# uC.net
KiCad netlist of a schematic drawn in Altium Designer
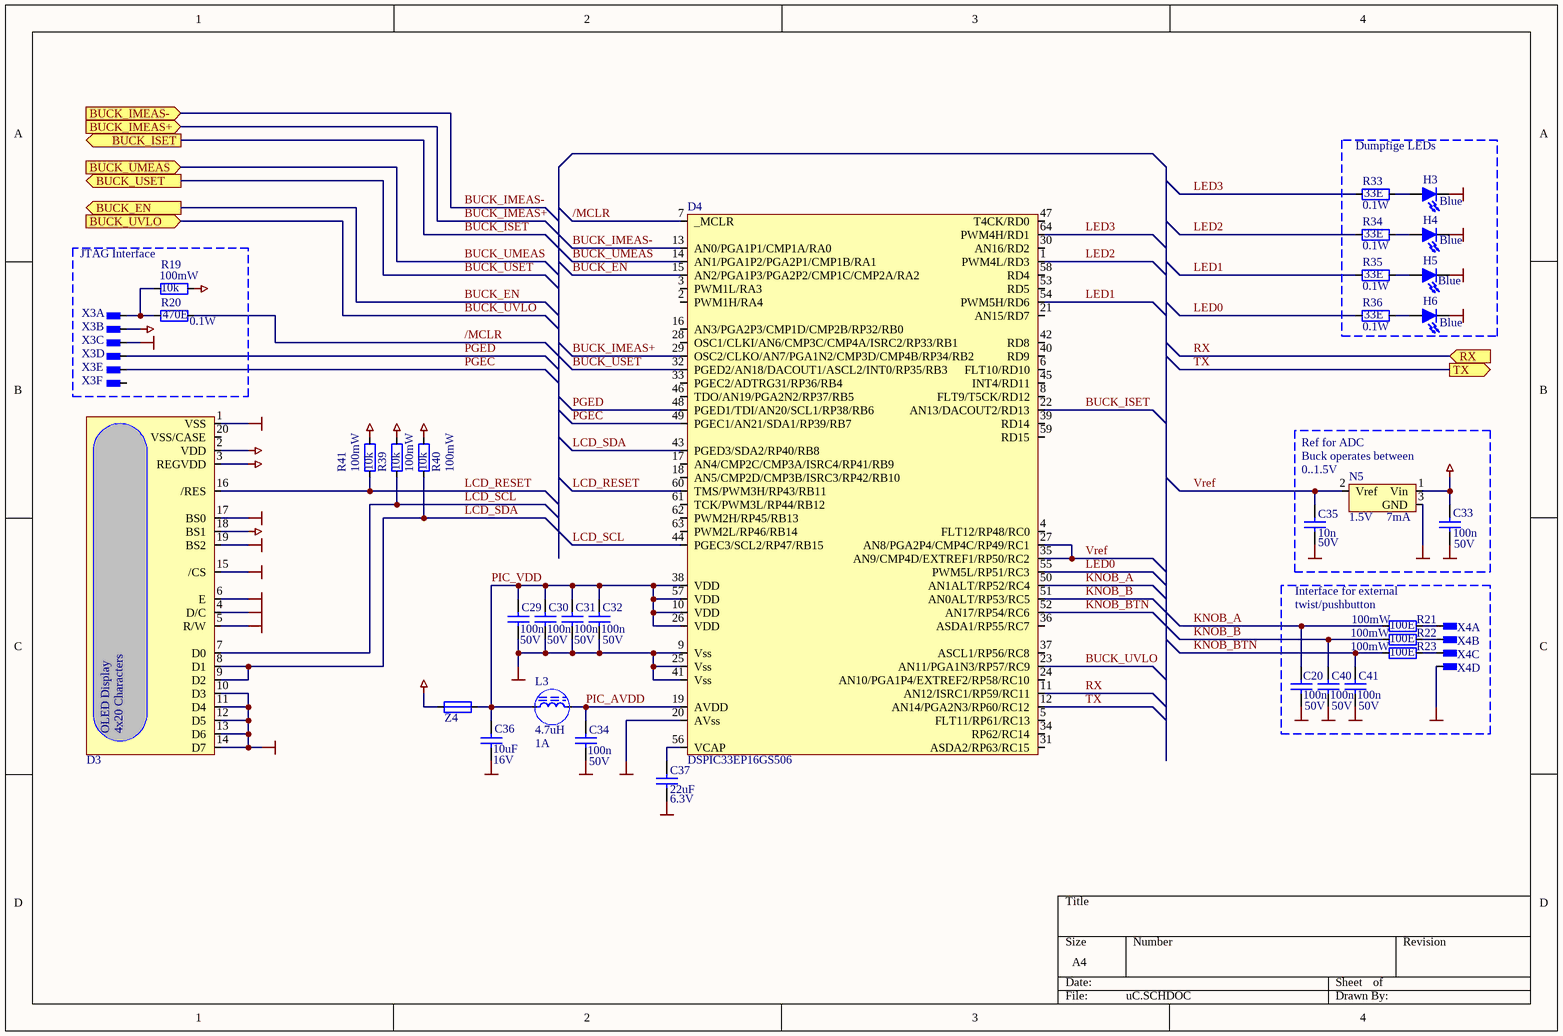
[diagram p0: uC.SCHDOC]

(export (version "E")
  (design (tool "Eeschema 10.0.6"))
  (components
    (comp (ref "C20")
      (value "C_SMD_CER_100N_50V_10%_X7R_0603")
      (footprint "SMD_0603")
      (description "SMD Capacitor")
      (fields (field (name "ALTIUM_VALUE") "100n") (field (name "VALUE2") "50V"))
      (libsource (lib "C-Capacitor") (part "C_SMD_CER_100N_50V_10%_X7R_0603"))
    )
    (comp (ref "C29")
      (value "C_SMD_CER_100N_50V_10%_X7R_0603")
      (footprint "SMD_0603")
      (description "SMD Capacitor")
      (fields (field (name "ALTIUM_VALUE") "100n") (field (name "VALUE2") "50V"))
      (libsource (lib "C-Capacitor") (part "C_SMD_CER_100N_50V_10%_X7R_0603"))
    )
    (comp (ref "C30")
      (value "C_SMD_CER_100N_50V_10%_X7R_0603")
      (footprint "SMD_0603")
      (description "SMD Capacitor")
      (fields (field (name "ALTIUM_VALUE") "100n") (field (name "VALUE2") "50V"))
      (libsource (lib "C-Capacitor") (part "C_SMD_CER_100N_50V_10%_X7R_0603"))
    )
    (comp (ref "C31")
      (value "C_SMD_CER_100N_50V_10%_X7R_0603")
      (footprint "SMD_0603")
      (description "SMD Capacitor")
      (fields (field (name "ALTIUM_VALUE") "100n") (field (name "VALUE2") "50V"))
      (libsource (lib "C-Capacitor") (part "C_SMD_CER_100N_50V_10%_X7R_0603"))
    )
    (comp (ref "C32")
      (value "C_SMD_CER_100N_50V_10%_X7R_0603")
      (footprint "SMD_0603")
      (description "SMD Capacitor")
      (fields (field (name "ALTIUM_VALUE") "100n") (field (name "VALUE2") "50V"))
      (libsource (lib "C-Capacitor") (part "C_SMD_CER_100N_50V_10%_X7R_0603"))
    )
    (comp (ref "C33")
      (value "C_SMD_CER_100N_50V_10%_X7R_0603")
      (footprint "SMD_0603")
      (description "SMD Capacitor")
      (fields (field (name "ALTIUM_VALUE") "100n") (field (name "VALUE2") "50V"))
      (libsource (lib "C-Capacitor") (part "C_SMD_CER_100N_50V_10%_X7R_0603"))
    )
    (comp (ref "C34")
      (value "C_SMD_CER_100N_50V_10%_X7R_0603")
      (footprint "SMD_0603")
      (description "SMD Capacitor")
      (fields (field (name "ALTIUM_VALUE") "100n") (field (name "VALUE2") "50V"))
      (libsource (lib "C-Capacitor") (part "C_SMD_CER_100N_50V_10%_X7R_0603"))
    )
    (comp (ref "C35")
      (value "C_SMD_CER_10N_50V_10%_X7R_0603")
      (footprint "SMD_0603")
      (description "SMD Capacitor")
      (fields (field (name "ALTIUM_VALUE") "10n") (field (name "VALUE2") "50V"))
      (libsource (lib "C-Capacitor") (part "C_SMD_CER_10N_50V_10%_X7R_0603"))
    )
    (comp (ref "C36")
      (value "C_SMD_CER_10U_16V_10%_X5R_0805")
      (footprint "SMD_0805")
      (description "SMD Capacitor")
      (fields (field (name "ALTIUM_VALUE") "10uF") (field (name "VALUE2") "16V"))
      (libsource (lib "C-Capacitor") (part "C_SMD_CER_10U_16V_10%_X5R_0805"))
    )
    (comp (ref "C37")
      (value "C_SMD_CER_22U_6V3_20%_X5R_1206")
      (footprint "SMD_1206")
      (description "SMD Capacitor")
      (fields (field (name "ALTIUM_VALUE") "22uF") (field (name "VALUE2") "6.3V"))
      (libsource (lib "C-Capacitor") (part "C_SMD_CER_22U_6V3_20%_X5R_1206"))
    )
    (comp (ref "C40")
      (value "C_SMD_CER_100N_50V_10%_X7R_0603")
      (footprint "SMD_0603")
      (description "SMD Capacitor")
      (fields (field (name "ALTIUM_VALUE") "100n") (field (name "VALUE2") "50V"))
      (libsource (lib "C-Capacitor") (part "C_SMD_CER_100N_50V_10%_X7R_0603"))
    )
    (comp (ref "C41")
      (value "C_SMD_CER_100N_50V_10%_X7R_0603")
      (footprint "SMD_0603")
      (description "SMD Capacitor")
      (fields (field (name "ALTIUM_VALUE") "100n") (field (name "VALUE2") "50V"))
      (libsource (lib "C-Capacitor") (part "C_SMD_CER_100N_50V_10%_X7R_0603"))
    )
    (comp (ref "D3")
      (value "D_LCD_80CHAR_20X4_NHD-0420CW-AR3")
      (footprint "THT_CON_P2.54_D0.9_2X10")
      (libsource (lib "D-Digital") (part "D_LCD_80CHAR_20X4_NHD-0420CW-AR3"))
    )
    (comp (ref "D4")
      (value "D_DSPIC33EP16GS506_TQFP-64")
      (footprint "SMD_TQFP-64")
      (fields (field (name "TYPE") "DSPIC33EP16GS506"))
      (libsource (lib "AM") (part "D_DSPIC33EP16GS506_TQFP-64"))
    )
    (comp (ref "H3")
      (value "H_SMD_LED_BLUE_0603")
      (footprint "SMD_0603P")
      (description "Blue LED, 5mA")
      (fields (field (name "TYPE") "Blue"))
      (libsource (lib "H-Signaling device") (part "H_SMD_LED_BLUE_0603"))
    )
    (comp (ref "H4")
      (value "H_SMD_LED_BLUE_0603")
      (footprint "SMD_0603P")
      (description "Blue LED, 5mA")
      (fields (field (name "TYPE") "Blue"))
      (libsource (lib "H-Signaling device") (part "H_SMD_LED_BLUE_0603"))
    )
    (comp (ref "H5")
      (value "H_SMD_LED_BLUE_0603")
      (footprint "SMD_0603P")
      (description "Blue LED, 5mA")
      (fields (field (name "TYPE") "Blue"))
      (libsource (lib "H-Signaling device") (part "H_SMD_LED_BLUE_0603"))
    )
    (comp (ref "H6")
      (value "H_SMD_LED_BLUE_0603")
      (footprint "SMD_0603P")
      (description "Blue LED, 5mA")
      (fields (field (name "TYPE") "Blue"))
      (libsource (lib "H-Signaling device") (part "H_SMD_LED_BLUE_0603"))
    )
    (comp (ref "L3")
      (value "L_SMD_4U7_1A_20%_0806")
      (footprint "SMD_0806")
      (description "SMD Inductor")
      (fields (field (name "ALTIUM_VALUE") "4.7uH") (field (name "VALUE2") "1A"))
      (libsource (lib "AM") (part "L_SMD_4U7_1A_20%_0806"))
    )
    (comp (ref "N5")
      (value "N_UREF_1V5_0A007_52UVRMS_ISL21080CIH315Z_SOT-23-3")
      (footprint "SMD_SOT_23_3")
      (fields (field (name "ALTIUM_VALUE") "1.5V") (field (name "VALUE2") "7mA"))
      (libsource (lib "AM") (part "N_UREF_1V5_0A007_52UVRMS_ISL21080CIH315Z_SOT-23-3"))
    )
    (comp (ref "R19")
      (value "R_SMD_THINFILM_10K_0W1_1%_50PPM_0603")
      (footprint "SMD_0603")
      (description "SMD Resistor")
      (fields (field (name "ALTIUM_VALUE") "10k") (field (name "VALUE2") "100mW"))
      (libsource (lib "R-Resistor") (part "R_SMD_THINFILM_10K_0W1_1%_50PPM_0603"))
    )
    (comp (ref "R20")
      (value "R_SMD_THINFILM_470E_0W1_1%_50PPM_0603")
      (footprint "SMD_0603")
      (description "SMD Resistor")
      (fields (field (name "ALTIUM_VALUE") "470E") (field (name "VALUE2") "0.1W"))
      (libsource (lib "AM") (part "R_SMD_THINFILM_470E_0W1_1%_50PPM_0603"))
    )
    (comp (ref "R21")
      (value "R_SMD_THINFILM_100E_0W1_1%_50PPM_0603")
      (footprint "SMD_0603")
      (description "SMD Resistor")
      (fields (field (name "ALTIUM_VALUE") "100E") (field (name "VALUE2") "100mW"))
      (libsource (lib "R-Resistor") (part "R_SMD_THINFILM_100E_0W1_1%_50PPM_0603"))
    )
    (comp (ref "R22")
      (value "R_SMD_THINFILM_100E_0W1_1%_50PPM_0603")
      (footprint "SMD_0603")
      (description "SMD Resistor")
      (fields (field (name "ALTIUM_VALUE") "100E") (field (name "VALUE2") "100mW"))
      (libsource (lib "R-Resistor") (part "R_SMD_THINFILM_100E_0W1_1%_50PPM_0603"))
    )
    (comp (ref "R23")
      (value "R_SMD_THINFILM_100E_0W1_1%_50PPM_0603")
      (footprint "SMD_0603")
      (description "SMD Resistor")
      (fields (field (name "ALTIUM_VALUE") "100E") (field (name "VALUE2") "100mW"))
      (libsource (lib "R-Resistor") (part "R_SMD_THINFILM_100E_0W1_1%_50PPM_0603"))
    )
    (comp (ref "R33")
      (value "R_SMD_THINFILM_33E_0W1_1%_50PPM_0603")
      (footprint "SMD_0603")
      (description "SMD Resistor")
      (fields (field (name "ALTIUM_VALUE") "33E") (field (name "VALUE2") "0.1W"))
      (libsource (lib "R-Resistor") (part "R_SMD_THINFILM_33E_0W1_1%_50PPM_0603"))
    )
    (comp (ref "R34")
      (value "R_SMD_THINFILM_33E_0W1_1%_50PPM_0603")
      (footprint "SMD_0603")
      (description "SMD Resistor")
      (fields (field (name "ALTIUM_VALUE") "33E") (field (name "VALUE2") "0.1W"))
      (libsource (lib "R-Resistor") (part "R_SMD_THINFILM_33E_0W1_1%_50PPM_0603"))
    )
    (comp (ref "R35")
      (value "R_SMD_THINFILM_33E_0W1_1%_50PPM_0603")
      (footprint "SMD_0603")
      (description "SMD Resistor")
      (fields (field (name "ALTIUM_VALUE") "33E") (field (name "VALUE2") "0.1W"))
      (libsource (lib "R-Resistor") (part "R_SMD_THINFILM_33E_0W1_1%_50PPM_0603"))
    )
    (comp (ref "R36")
      (value "R_SMD_THINFILM_33E_0W1_1%_50PPM_0603")
      (footprint "SMD_0603")
      (description "SMD Resistor")
      (fields (field (name "ALTIUM_VALUE") "33E") (field (name "VALUE2") "0.1W"))
      (libsource (lib "R-Resistor") (part "R_SMD_THINFILM_33E_0W1_1%_50PPM_0603"))
    )
    (comp (ref "R39")
      (value "R_SMD_THINFILM_10K_0W1_1%_50PPM_0603")
      (footprint "SMD_0603")
      (description "SMD Resistor")
      (fields (field (name "ALTIUM_VALUE") "10k") (field (name "VALUE2") "100mW"))
      (libsource (lib "AM") (part "R_SMD_THINFILM_10K_0W1_1%_50PPM_0603"))
    )
    (comp (ref "R40")
      (value "R_SMD_THINFILM_10K_0W1_1%_50PPM_0603")
      (footprint "SMD_0603")
      (description "SMD Resistor")
      (fields (field (name "ALTIUM_VALUE") "10k") (field (name "VALUE2") "100mW"))
      (libsource (lib "AM") (part "R_SMD_THINFILM_10K_0W1_1%_50PPM_0603"))
    )
    (comp (ref "R41")
      (value "R_SMD_THINFILM_10K_0W1_1%_50PPM_0603")
      (footprint "SMD_0603")
      (description "SMD Resistor")
      (fields (field (name "ALTIUM_VALUE") "10k") (field (name "VALUE2") "100mW"))
      (libsource (lib "AM") (part "R_SMD_THINFILM_10K_0W1_1%_50PPM_0603"))
    )
    (comp (ref "X3")
      (value "X_CONNECTOR_P2.54_D0.9_1X6")
      (footprint "THT_CON_P2.54_D0.9_1X6")
      (description "Pitch 2.54, Diameter 0.9mm, 1 row, 6 columns")
      (libsource (lib "AM") (part "X_CONNECTOR_P2.54_D0.9_1X6"))
    )
    (comp (ref "X4")
      (value "X_CONNECTOR_P2.54_D0.9_1X4")
      (footprint "THT_CON_P2.54_D0.9_1X4")
      (description "Pitch 2.54, Diameter 0.9mm, 1 row, 4 columns")
      (libsource (lib "AM") (part "X_CONNECTOR_P2.54_D0.9_1X4"))
    )
    (comp (ref "Z4")
      (value "Z_SMD_FERRITE_1A5_470E@100MHZ_0603")
      (footprint "SMD_0603")
      (description "FERRITE CHIP 470 OHM 1500MA 0603")
      (libsource (lib "AM") (part "Z_SMD_FERRITE_1A5_470E@100MHZ_0603"))
    )
  )
  (nets
    (net (code "1") (name "+3.3V") (class "Default")
      (node (ref "C33") (pin "2") (pinfunction "2_2") (pintype "passive"))
      (node (ref "N5") (pin "1") (pinfunction "Vin_1") (pintype "passive"))
      (node (ref "R19") (pin "2") (pinfunction "2_2") (pintype "passive"))
      (node (ref "X3") (pin "2") (pinfunction "2_2") (pintype "passive"))
      (node (ref "Z4") (pin "2") (pinfunction "2_2") (pintype "passive"))
    )
    (net (code "2") (name "+5V") (class "Default")
      (node (ref "D3") (pin "18") (pinfunction "BS1_18") (pintype "passive"))
      (node (ref "D3") (pin "2") (pinfunction "VDD_2") (pintype "passive"))
      (node (ref "D3") (pin "3") (pinfunction "REGVDD_3") (pintype "passive"))
      (node (ref "R39") (pin "2") (pinfunction "2_2") (pintype "passive"))
      (node (ref "R40") (pin "2") (pinfunction "2_2") (pintype "passive"))
      (node (ref "R41") (pin "2") (pinfunction "2_2") (pintype "passive"))
    )
    (net (code "3") (name "/BUCK_EN") (class "Default")
      (node (ref "D4") (pin "15") (pinfunction "AN2/PGA1P3/PGA2P2/CMP1C/CMP2A/RA2_15") (pintype "passive"))
    )
    (net (code "4") (name "/BUCK_IMEAS+") (class "Default")
      (node (ref "D4") (pin "29") (pinfunction "OSC2/CLKO/AN7/PGA1N2/CMP3D/CMP4B/RP34/RB2_29") (pintype "passive"))
    )
    (net (code "5") (name "/BUCK_IMEAS-") (class "Default")
      (node (ref "D4") (pin "13") (pinfunction "AN0/PGA1P1/CMP1A/RA0_13") (pintype "passive"))
    )
    (net (code "6") (name "/BUCK_ISET") (class "Default")
      (node (ref "D4") (pin "22") (pinfunction "AN13/DACOUT2/RD13_22") (pintype "passive"))
    )
    (net (code "7") (name "/BUCK_UMEAS") (class "Default")
      (node (ref "D4") (pin "14") (pinfunction "AN1/PGA1P2/PGA2P1/CMP1B/RA1_14") (pintype "passive"))
    )
    (net (code "8") (name "/BUCK_USET") (class "Default")
      (node (ref "D4") (pin "32") (pinfunction "PGED2/AN18/DACOUT1/ASCL2/INT0/RP35/RB3_32") (pintype "passive"))
    )
    (net (code "9") (name "/BUCK_UVLO") (class "Default")
      (node (ref "D4") (pin "23") (pinfunction "AN11/PGA1N3/RP57/RC9_23") (pintype "passive"))
    )
    (net (code "10") (name "/KNOB_A") (class "Default")
      (node (ref "C20") (pin "2") (pinfunction "2_2") (pintype "passive"))
      (node (ref "D4") (pin "50") (pinfunction "AN1ALT/RP52/RC4_50") (pintype "passive"))
      (node (ref "R21") (pin "1") (pinfunction "1_1") (pintype "passive"))
    )
    (net (code "11") (name "/KNOB_B") (class "Default")
      (node (ref "C40") (pin "2") (pinfunction "2_2") (pintype "passive"))
      (node (ref "D4") (pin "51") (pinfunction "AN0ALT/RP53/RC5_51") (pintype "passive"))
      (node (ref "R22") (pin "1") (pinfunction "1_1") (pintype "passive"))
    )
    (net (code "12") (name "/KNOB_BTN") (class "Default")
      (node (ref "C41") (pin "2") (pinfunction "2_2") (pintype "passive"))
      (node (ref "D4") (pin "52") (pinfunction "AN17/RP54/RC6_52") (pintype "passive"))
      (node (ref "R23") (pin "1") (pinfunction "1_1") (pintype "passive"))
    )
    (net (code "13") (name "/LCD_RESET") (class "Default")
      (node (ref "D3") (pin "16") (pinfunction "/RES_16") (pintype "passive"))
      (node (ref "D4") (pin "60") (pinfunction "TMS/PWM3H/RP43/RB11_60") (pintype "passive"))
      (node (ref "R41") (pin "1") (pinfunction "1_1") (pintype "passive"))
    )
    (net (code "14") (name "/LCD_SCL") (class "Default")
      (node (ref "D3") (pin "7") (pinfunction "D0_7") (pintype "passive"))
      (node (ref "D4") (pin "44") (pinfunction "PGEC3/SCL2/RP47/RB15_44") (pintype "passive"))
      (node (ref "R39") (pin "1") (pinfunction "1_1") (pintype "passive"))
    )
    (net (code "15") (name "/LCD_SDA") (class "Default")
      (node (ref "D3") (pin "8") (pinfunction "D1_8") (pintype "passive"))
      (node (ref "D3") (pin "9") (pinfunction "D2_9") (pintype "passive"))
      (node (ref "D4") (pin "43") (pinfunction "PGED3/SDA2/RP40/RB8_43") (pintype "passive"))
      (node (ref "R40") (pin "1") (pinfunction "1_1") (pintype "passive"))
    )
    (net (code "16") (name "/LED0") (class "Default")
      (node (ref "D4") (pin "55") (pinfunction "PWM5L/RP51/RC3_55") (pintype "passive"))
      (node (ref "R36") (pin "1") (pinfunction "1_1") (pintype "passive"))
    )
    (net (code "17") (name "/LED1") (class "Default")
      (node (ref "D4") (pin "54") (pinfunction "PWM5H/RD6_54") (pintype "passive"))
      (node (ref "R35") (pin "1") (pinfunction "1_1") (pintype "passive"))
    )
    (net (code "18") (name "/LED2") (class "Default")
      (node (ref "D4") (pin "1") (pinfunction "PWM4L/RD3_1") (pintype "passive"))
      (node (ref "R34") (pin "1") (pinfunction "1_1") (pintype "passive"))
    )
    (net (code "19") (name "/LED3") (class "Default")
      (node (ref "D4") (pin "64") (pinfunction "PWM4H/RD1_64") (pintype "passive"))
      (node (ref "R33") (pin "1") (pinfunction "1_1") (pintype "passive"))
    )
    (net (code "20") (name "/PGEC") (class "Default")
      (node (ref "D4") (pin "49") (pinfunction "PGEC1/AN21/SDA1/RP39/RB7_49") (pintype "passive"))
      (node (ref "X3") (pin "5") (pinfunction "5_5") (pintype "passive"))
    )
    (net (code "21") (name "/PGED") (class "Default")
      (node (ref "D4") (pin "48") (pinfunction "PGED1/TDI/AN20/SCL1/RP38/RB6_48") (pintype "passive"))
      (node (ref "X3") (pin "4") (pinfunction "4_4") (pintype "passive"))
    )
    (net (code "22") (name "/PIC_AVDD") (class "Default")
      (node (ref "C34") (pin "2") (pinfunction "2_2") (pintype "passive"))
      (node (ref "D4") (pin "19") (pinfunction "AVDD_19") (pintype "passive"))
      (node (ref "L3") (pin "2") (pinfunction "2_2") (pintype "passive"))
    )
    (net (code "23") (name "/PIC_VDD") (class "Default")
      (node (ref "C29") (pin "2") (pinfunction "2_2") (pintype "passive"))
      (node (ref "C30") (pin "2") (pinfunction "2_2") (pintype "passive"))
      (node (ref "C31") (pin "2") (pinfunction "2_2") (pintype "passive"))
      (node (ref "C32") (pin "2") (pinfunction "2_2") (pintype "passive"))
      (node (ref "C36") (pin "2") (pinfunction "2_2") (pintype "passive"))
      (node (ref "D4") (pin "10") (pinfunction "VDD_10") (pintype "passive"))
      (node (ref "D4") (pin "26") (pinfunction "VDD_26") (pintype "passive"))
      (node (ref "D4") (pin "38") (pinfunction "VDD_38") (pintype "passive"))
      (node (ref "D4") (pin "57") (pinfunction "VDD_57") (pintype "passive"))
      (node (ref "L3") (pin "1") (pinfunction "1_1") (pintype "passive"))
      (node (ref "Z4") (pin "1") (pinfunction "1_1") (pintype "passive"))
    )
    (net (code "24") (name "/RX") (class "Default")
      (node (ref "D4") (pin "11") (pinfunction "AN12/ISRC1/RP59/RC11_11") (pintype "passive"))
    )
    (net (code "25") (name "/TX") (class "Default")
      (node (ref "D4") (pin "12") (pinfunction "AN14/PGA2N3/RP60/RC12_12") (pintype "passive"))
    )
    (net (code "26") (name "/Vref") (class "Default")
      (node (ref "C35") (pin "2") (pinfunction "2_2") (pintype "passive"))
      (node (ref "D4") (pin "27") (pinfunction "AN8/PGA2P4/CMP4C/RP49/RC1_27") (pintype "passive"))
      (node (ref "D4") (pin "35") (pinfunction "AN9/CMP4D/EXTREF1/RP50/RC2_35") (pintype "passive"))
      (node (ref "N5") (pin "2") (pinfunction "Vref_2") (pintype "passive"))
    )
    (net (code "27") (name "/{slash}MCLR") (class "Default")
      (node (ref "D4") (pin "7") (pinfunction "_MCLR_7") (pintype "passive"))
      (node (ref "R20") (pin "2") (pinfunction "2_2") (pintype "passive"))
    )
    (net (code "28") (name "GND") (class "Default")
      (node (ref "C20") (pin "1") (pinfunction "1_1") (pintype "passive"))
      (node (ref "C29") (pin "1") (pinfunction "1_1") (pintype "passive"))
      (node (ref "C30") (pin "1") (pinfunction "1_1") (pintype "passive"))
      (node (ref "C31") (pin "1") (pinfunction "1_1") (pintype "passive"))
      (node (ref "C32") (pin "1") (pinfunction "1_1") (pintype "passive"))
      (node (ref "C33") (pin "1") (pinfunction "1_1") (pintype "passive"))
      (node (ref "C34") (pin "1") (pinfunction "1_1") (pintype "passive"))
      (node (ref "C35") (pin "1") (pinfunction "1_1") (pintype "passive"))
      (node (ref "C36") (pin "1") (pinfunction "1_1") (pintype "passive"))
      (node (ref "C37") (pin "1") (pinfunction "1_1") (pintype "passive"))
      (node (ref "C40") (pin "1") (pinfunction "1_1") (pintype "passive"))
      (node (ref "C41") (pin "1") (pinfunction "1_1") (pintype "passive"))
      (node (ref "D3") (pin "1") (pinfunction "VSS_1") (pintype "passive"))
      (node (ref "D3") (pin "10") (pinfunction "D3_10") (pintype "passive"))
      (node (ref "D3") (pin "11") (pinfunction "D4_11") (pintype "passive"))
      (node (ref "D3") (pin "12") (pinfunction "D5_12") (pintype "passive"))
      (node (ref "D3") (pin "13") (pinfunction "D6_13") (pintype "passive"))
      (node (ref "D3") (pin "14") (pinfunction "D7_14") (pintype "passive"))
      (node (ref "D3") (pin "15") (pinfunction "/CS_15") (pintype "passive"))
      (node (ref "D3") (pin "17") (pinfunction "BS0_17") (pintype "passive"))
      (node (ref "D3") (pin "19") (pinfunction "BS2_19") (pintype "passive"))
      (node (ref "D3") (pin "4") (pinfunction "D/C_4") (pintype "passive"))
      (node (ref "D3") (pin "5") (pinfunction "R/W_5") (pintype "passive"))
      (node (ref "D3") (pin "6") (pinfunction "E_6") (pintype "passive"))
      (node (ref "D4") (pin "20") (pinfunction "AVss_20") (pintype "passive"))
      (node (ref "D4") (pin "25") (pinfunction "Vss_25") (pintype "passive"))
      (node (ref "D4") (pin "41") (pinfunction "Vss_41") (pintype "passive"))
      (node (ref "D4") (pin "9") (pinfunction "Vss_9") (pintype "passive"))
      (node (ref "H3") (pin "2") (pinfunction "2_2") (pintype "passive"))
      (node (ref "H4") (pin "2") (pinfunction "2_2") (pintype "passive"))
      (node (ref "H5") (pin "2") (pinfunction "2_2") (pintype "passive"))
      (node (ref "H6") (pin "2") (pinfunction "2_2") (pintype "passive"))
      (node (ref "N5") (pin "3") (pinfunction "GND_3") (pintype "passive"))
      (node (ref "X3") (pin "3") (pinfunction "3_3") (pintype "passive"))
      (node (ref "X4") (pin "4") (pinfunction "4_4") (pintype "passive"))
    )
    (net (code "29") (name "Net-(D4-VCAP)") (class "Default")
      (node (ref "C37") (pin "2") (pinfunction "2_2") (pintype "passive"))
      (node (ref "D4") (pin "56") (pinfunction "VCAP_56") (pintype "passive"))
    )
    (net (code "30") (name "Net-(H3-Pad1)") (class "Default")
      (node (ref "H3") (pin "1") (pinfunction "1_1") (pintype "passive"))
      (node (ref "R33") (pin "2") (pinfunction "2_2") (pintype "passive"))
    )
    (net (code "31") (name "Net-(H4-Pad1)") (class "Default")
      (node (ref "H4") (pin "1") (pinfunction "1_1") (pintype "passive"))
      (node (ref "R34") (pin "2") (pinfunction "2_2") (pintype "passive"))
    )
    (net (code "32") (name "Net-(H5-Pad1)") (class "Default")
      (node (ref "H5") (pin "1") (pinfunction "1_1") (pintype "passive"))
      (node (ref "R35") (pin "2") (pinfunction "2_2") (pintype "passive"))
    )
    (net (code "33") (name "Net-(H6-Pad1)") (class "Default")
      (node (ref "H6") (pin "1") (pinfunction "1_1") (pintype "passive"))
      (node (ref "R36") (pin "2") (pinfunction "2_2") (pintype "passive"))
    )
    (net (code "34") (name "Net-(R19-Pad1)") (class "Default")
      (node (ref "R19") (pin "1") (pinfunction "1_1") (pintype "passive"))
      (node (ref "R20") (pin "1") (pinfunction "1_1") (pintype "passive"))
      (node (ref "X3") (pin "1") (pinfunction "1_1") (pintype "passive"))
    )
    (net (code "35") (name "Net-(R21-Pad2)") (class "Default")
      (node (ref "R21") (pin "2") (pinfunction "2_2") (pintype "passive"))
      (node (ref "X4") (pin "1") (pinfunction "1_1") (pintype "passive"))
    )
    (net (code "36") (name "Net-(R22-Pad2)") (class "Default")
      (node (ref "R22") (pin "2") (pinfunction "2_2") (pintype "passive"))
      (node (ref "X4") (pin "2") (pinfunction "2_2") (pintype "passive"))
    )
    (net (code "37") (name "Net-(R23-Pad2)") (class "Default")
      (node (ref "R23") (pin "2") (pinfunction "2_2") (pintype "passive"))
      (node (ref "X4") (pin "3") (pinfunction "3_3") (pintype "passive"))
    )
    (net (code "38") (name "unconnected-(D3-VSS{slash}CASE-Pad20)") (class "Default")
      (node (ref "D3") (pin "20") (pinfunction "VSS/CASE_20") (pintype "passive"))
    )
    (net (code "39") (name "unconnected-(D4-AN3{slash}PGA2P3{slash}CMP1D{slash}CMP2B{slash}RP32{slash}RB0-Pad16)") (class "Default")
      (node (ref "D4") (pin "16") (pinfunction "AN3/PGA2P3/CMP1D/CMP2B/RP32/RB0_16") (pintype "passive"))
    )
    (net (code "40") (name "unconnected-(D4-AN4{slash}CMP2C{slash}CMP3A{slash}ISRC4{slash}RP41{slash}RB9-Pad17)") (class "Default")
      (node (ref "D4") (pin "17") (pinfunction "AN4/CMP2C/CMP3A/ISRC4/RP41/RB9_17") (pintype "passive"))
    )
    (net (code "41") (name "unconnected-(D4-AN5{slash}CMP2D{slash}CMP3B{slash}ISRC3{slash}RP42{slash}RB10-Pad18)") (class "Default")
      (node (ref "D4") (pin "18") (pinfunction "AN5/CMP2D/CMP3B/ISRC3/RP42/RB10_18") (pintype "passive"))
    )
    (net (code "42") (name "unconnected-(D4-AN10{slash}PGA1P4{slash}EXTREF2{slash}RP58{slash}RC10-Pad24)") (class "Default")
      (node (ref "D4") (pin "24") (pinfunction "AN10/PGA1P4/EXTREF2/RP58/RC10_24") (pintype "passive"))
    )
    (net (code "43") (name "unconnected-(D4-AN15{slash}RD7-Pad21)") (class "Default")
      (node (ref "D4") (pin "21") (pinfunction "AN15/RD7_21") (pintype "passive"))
    )
    (net (code "44") (name "unconnected-(D4-AN16{slash}RD2-Pad30)") (class "Default")
      (node (ref "D4") (pin "30") (pinfunction "AN16/RD2_30") (pintype "passive"))
    )
    (net (code "45") (name "unconnected-(D4-ASCL1{slash}RP56{slash}RC8-Pad37)") (class "Default")
      (node (ref "D4") (pin "37") (pinfunction "ASCL1/RP56/RC8_37") (pintype "passive"))
    )
    (net (code "46") (name "unconnected-(D4-ASDA1{slash}RP55{slash}RC7-Pad36)") (class "Default")
      (node (ref "D4") (pin "36") (pinfunction "ASDA1/RP55/RC7_36") (pintype "passive"))
    )
    (net (code "47") (name "unconnected-(D4-ASDA2{slash}RP63{slash}RC15-Pad31)") (class "Default")
      (node (ref "D4") (pin "31") (pinfunction "ASDA2/RP63/RC15_31") (pintype "passive"))
    )
    (net (code "48") (name "unconnected-(D4-FLT9{slash}T5CK{slash}RD12-Pad8)") (class "Default")
      (node (ref "D4") (pin "8") (pinfunction "FLT9/T5CK/RD12_8") (pintype "passive"))
    )
    (net (code "49") (name "unconnected-(D4-FLT10{slash}RD10-Pad6)") (class "Default")
      (node (ref "D4") (pin "6") (pinfunction "FLT10/RD10_6") (pintype "passive"))
    )
    (net (code "50") (name "unconnected-(D4-FLT11{slash}RP61{slash}RC13-Pad5)") (class "Default")
      (node (ref "D4") (pin "5") (pinfunction "FLT11/RP61/RC13_5") (pintype "passive"))
    )
    (net (code "51") (name "unconnected-(D4-FLT12{slash}RP48{slash}RC0-Pad4)") (class "Default")
      (node (ref "D4") (pin "4") (pinfunction "FLT12/RP48/RC0_4") (pintype "passive"))
    )
    (net (code "52") (name "unconnected-(D4-INT4{slash}RD11-Pad45)") (class "Default")
      (node (ref "D4") (pin "45") (pinfunction "INT4/RD11_45") (pintype "passive"))
    )
    (net (code "53") (name "unconnected-(D4-OSC1{slash}CLKI{slash}AN6{slash}CMP3C{slash}CMP4A{slash}ISRC2{slash}RP33{slash}RB1-Pad28)") (class "Default")
      (node (ref "D4") (pin "28") (pinfunction "OSC1/CLKI/AN6/CMP3C/CMP4A/ISRC2/RP33/RB1_28") (pintype "passive"))
    )
    (net (code "54") (name "unconnected-(D4-PGEC2{slash}ADTRG31{slash}RP36{slash}RB4-Pad33)") (class "Default")
      (node (ref "D4") (pin "33") (pinfunction "PGEC2/ADTRG31/RP36/RB4_33") (pintype "passive"))
    )
    (net (code "55") (name "unconnected-(D4-PWM1H{slash}RA4-Pad2)") (class "Default")
      (node (ref "D4") (pin "2") (pinfunction "PWM1H/RA4_2") (pintype "passive"))
    )
    (net (code "56") (name "unconnected-(D4-PWM1L{slash}RA3-Pad3)") (class "Default")
      (node (ref "D4") (pin "3") (pinfunction "PWM1L/RA3_3") (pintype "passive"))
    )
    (net (code "57") (name "unconnected-(D4-PWM2H{slash}RP45{slash}RB13-Pad62)") (class "Default")
      (node (ref "D4") (pin "62") (pinfunction "PWM2H/RP45/RB13_62") (pintype "passive"))
    )
    (net (code "58") (name "unconnected-(D4-PWM2L{slash}RP46{slash}RB14-Pad63)") (class "Default")
      (node (ref "D4") (pin "63") (pinfunction "PWM2L/RP46/RB14_63") (pintype "passive"))
    )
    (net (code "59") (name "unconnected-(D4-RD4-Pad58)") (class "Default")
      (node (ref "D4") (pin "58") (pinfunction "RD4_58") (pintype "passive"))
    )
    (net (code "60") (name "unconnected-(D4-RD5-Pad53)") (class "Default")
      (node (ref "D4") (pin "53") (pinfunction "RD5_53") (pintype "passive"))
    )
    (net (code "61") (name "unconnected-(D4-RD8-Pad42)") (class "Default")
      (node (ref "D4") (pin "42") (pinfunction "RD8_42") (pintype "passive"))
    )
    (net (code "62") (name "unconnected-(D4-RD9-Pad40)") (class "Default")
      (node (ref "D4") (pin "40") (pinfunction "RD9_40") (pintype "passive"))
    )
    (net (code "63") (name "unconnected-(D4-RD14-Pad39)") (class "Default")
      (node (ref "D4") (pin "39") (pinfunction "RD14_39") (pintype "passive"))
    )
    (net (code "64") (name "unconnected-(D4-RD15-Pad59)") (class "Default")
      (node (ref "D4") (pin "59") (pinfunction "RD15_59") (pintype "passive"))
    )
    (net (code "65") (name "unconnected-(D4-RP62{slash}RC14-Pad34)") (class "Default")
      (node (ref "D4") (pin "34") (pinfunction "RP62/RC14_34") (pintype "passive"))
    )
    (net (code "66") (name "unconnected-(D4-T4CK{slash}RD0-Pad47)") (class "Default")
      (node (ref "D4") (pin "47") (pinfunction "T4CK/RD0_47") (pintype "passive"))
    )
    (net (code "67") (name "unconnected-(D4-TCK{slash}PWM3L{slash}RP44{slash}RB12-Pad61)") (class "Default")
      (node (ref "D4") (pin "61") (pinfunction "TCK/PWM3L/RP44/RB12_61") (pintype "passive"))
    )
    (net (code "68") (name "unconnected-(D4-TDO{slash}AN19{slash}PGA2N2{slash}RP37{slash}RB5-Pad46)") (class "Default")
      (node (ref "D4") (pin "46") (pinfunction "TDO/AN19/PGA2N2/RP37/RB5_46") (pintype "passive"))
    )
    (net (code "69") (name "unconnected-(X3-Pad6)") (class "Default")
      (node (ref "X3") (pin "6") (pinfunction "6_6") (pintype "passive"))
    )
  )
)
